# QiCape-v0_1.net
KiCad netlist of a schematic drawn in EAGLE
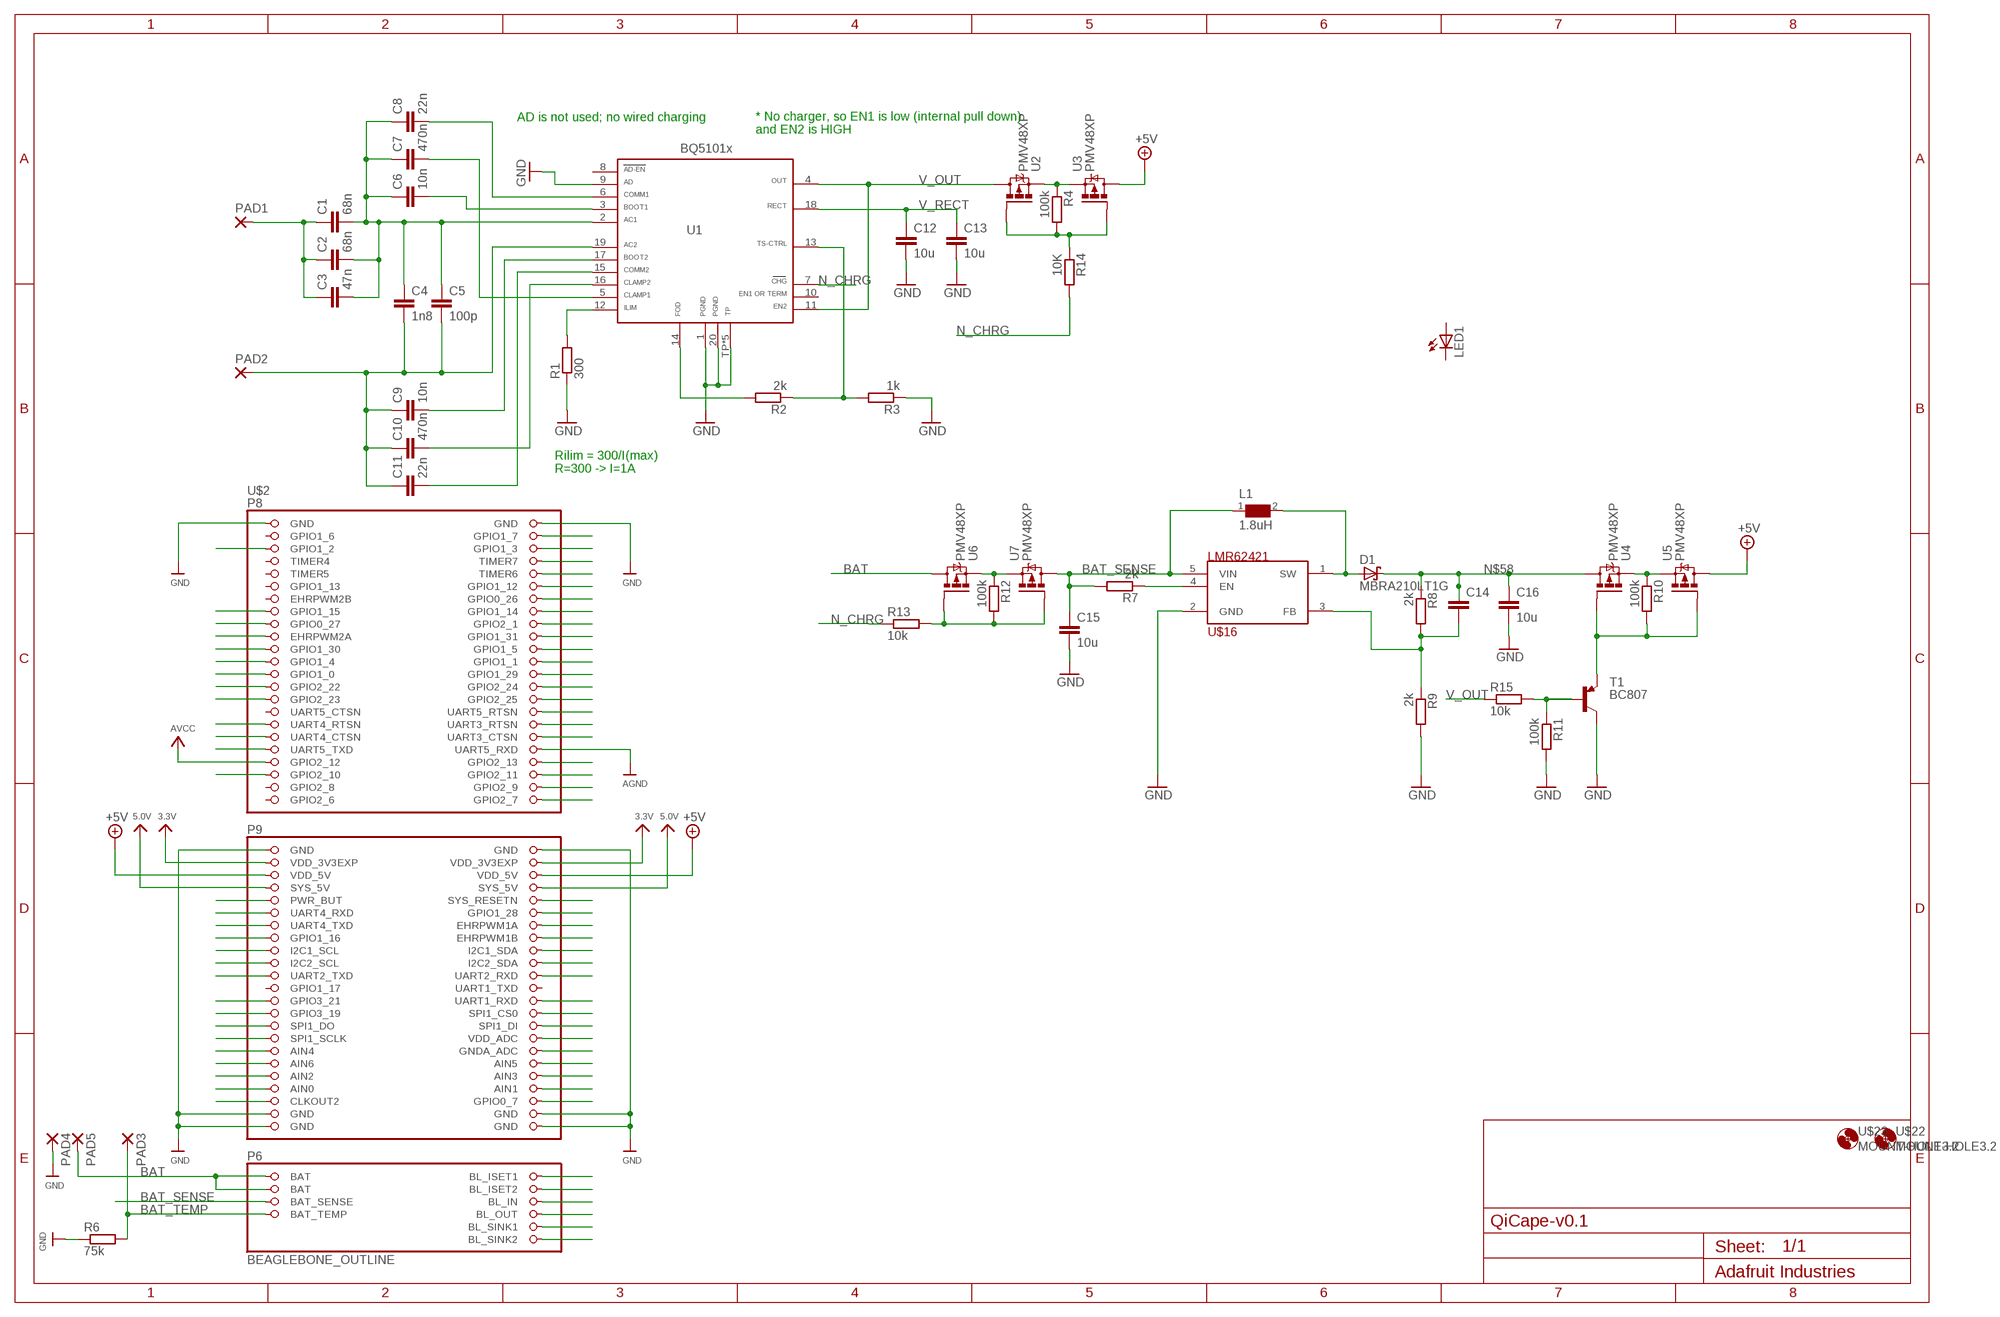
[diagram p0: schematic, sheet 1]

(export (version "E")
  (design (tool "Eeschema 10.0.6"))
  (components
    (comp (ref "C1")
      (value "68n")
      (footprint "eagle-import:C0603K")
      (fields (field (name "MF") "KEMET") (field (name "MPN") "C0603C682K5RACTU"))
      (libsource (lib "eagle-import") (part "C-EUC0603K"))
    )
    (comp (ref "C2")
      (value "68n")
      (footprint "eagle-import:C0603K")
      (fields (field (name "MF") "KEMET") (field (name "MPN") "C0603C682K5RACTU"))
      (libsource (lib "eagle-import") (part "C-EUC0603K"))
    )
    (comp (ref "C3")
      (value "47n")
      (footprint "eagle-import:C0603K")
      (fields (field (name "MPN") "C0603C473K5RACTU"))
      (libsource (lib "eagle-import") (part "C-EUC0603K"))
    )
    (comp (ref "C4")
      (value "1n8")
      (footprint "eagle-import:C0603K")
      (fields (field (name "MPN") "C0603C182K5RACTU"))
      (libsource (lib "eagle-import") (part "C-EUC0603K"))
    )
    (comp (ref "C5")
      (value "100p")
      (footprint "eagle-import:C0603K")
      (fields (field (name "MF") "KEMET") (field (name "MPN") "C0603C101K5RACTU"))
      (libsource (lib "eagle-import") (part "C-EUC0603K"))
    )
    (comp (ref "C6")
      (value "10n")
      (footprint "eagle-import:C0603K")
      (libsource (lib "eagle-import") (part "C-EUC0603K"))
    )
    (comp (ref "C7")
      (value "470n")
      (footprint "eagle-import:C0603K")
      (libsource (lib "eagle-import") (part "C-EUC0603K"))
    )
    (comp (ref "C8")
      (value "22n")
      (footprint "eagle-import:C0603K")
      (fields (field (name "MF") "KEMET") (field (name "MPN") "C0603C223K5RACTU"))
      (libsource (lib "eagle-import") (part "C-EUC0603K"))
    )
    (comp (ref "C9")
      (value "10n")
      (footprint "eagle-import:C0603K")
      (libsource (lib "eagle-import") (part "C-EUC0603K"))
    )
    (comp (ref "C10")
      (value "470n")
      (footprint "eagle-import:C0603K")
      (libsource (lib "eagle-import") (part "C-EUC0603K"))
    )
    (comp (ref "C11")
      (value "22n")
      (footprint "eagle-import:C0603K")
      (fields (field (name "MF") "KEMET") (field (name "MPN") "C0603C223K5RACTU"))
      (libsource (lib "eagle-import") (part "C-EUC0603K"))
    )
    (comp (ref "C12")
      (value "10u")
      (footprint "eagle-import:C0805")
      (fields (field (name "MPN") "GRM21BR61E106KA73L"))
      (libsource (lib "eagle-import") (part "C-EUC0805"))
    )
    (comp (ref "C13")
      (value "10u")
      (footprint "eagle-import:C0805")
      (fields (field (name "MPN") "GRM21BR61E106KA73L"))
      (libsource (lib "eagle-import") (part "C-EUC0805"))
    )
    (comp (ref "C14")
      (value "C-EUC0402")
      (footprint "eagle-import:C0402")
      (libsource (lib "eagle-import") (part "C-EUC0402"))
    )
    (comp (ref "C15")
      (value "10u")
      (footprint "eagle-import:C0805")
      (fields (field (name "MPN") "GRM21BR61E106KA73L"))
      (libsource (lib "eagle-import") (part "C-EUC0805"))
    )
    (comp (ref "C16")
      (value "10u")
      (footprint "eagle-import:C1206")
      (fields (field (name "MPN") "C3216X5R0J106K"))
      (libsource (lib "eagle-import") (part "C-EUC1206"))
    )
    (comp (ref "D1")
      (value "MBRA210LT1G")
      (footprint "eagle-import:SMA-DO214AC")
      (libsource (lib "eagle-import") (part "SCHOTTKY-DIODEMBRA210LT3G"))
    )
    (comp (ref "L1")
      (value "1.8uH")
      (footprint "eagle-import:WE-TPC_5818_5828")
      (fields (field (name "MPN") "7440520018"))
      (libsource (lib "eagle-import") (part "WE-TPC_5818/5828"))
    )
    (comp (ref "LED1")
      (value "LEDCHIP-LED0603")
      (footprint "eagle-import:CHIP-LED0603")
      (libsource (lib "eagle-import") (part "LEDCHIP-LED0603"))
    )
    (comp (ref "PAD1")
      (value "1,6/0,8")
      (footprint "eagle-import:1,6_0,8")
      (libsource (lib "eagle-import") (part "1,6/0,8"))
    )
    (comp (ref "PAD2")
      (value "1,6/0,8")
      (footprint "eagle-import:1,6_0,8")
      (libsource (lib "eagle-import") (part "1,6/0,8"))
    )
    (comp (ref "PAD3")
      (value "1,6/0,8")
      (footprint "eagle-import:1,6_0,8")
      (libsource (lib "eagle-import") (part "1,6/0,8"))
    )
    (comp (ref "PAD4")
      (value "1,6/0,8")
      (footprint "eagle-import:1,6_0,8")
      (libsource (lib "eagle-import") (part "1,6/0,8"))
    )
    (comp (ref "PAD5")
      (value "1,6/0,8")
      (footprint "eagle-import:1,6_0,8")
      (libsource (lib "eagle-import") (part "1,6/0,8"))
    )
    (comp (ref "R1")
      (value "300")
      (footprint "eagle-import:R0402")
      (fields (field (name "MPN") "ERJ3EKF3000V"))
      (libsource (lib "eagle-import") (part "R-EU_R0402"))
    )
    (comp (ref "R2")
      (value "2k")
      (footprint "eagle-import:R0402")
      (fields (field (name "MPN") "ERJ3EKF3000V"))
      (libsource (lib "eagle-import") (part "R-EU_R0402"))
    )
    (comp (ref "R3")
      (value "1k")
      (footprint "eagle-import:R0402")
      (fields (field (name "MPN") "ERJ3EKF3000V"))
      (libsource (lib "eagle-import") (part "R-EU_R0402"))
    )
    (comp (ref "R4")
      (value "100k")
      (footprint "eagle-import:R0402")
      (fields (field (name "MPN") "ERJ3EKF3000V"))
      (libsource (lib "eagle-import") (part "R-EU_R0402"))
    )
    (comp (ref "R6")
      (value "75k")
      (footprint "eagle-import:R0402")
      (fields (field (name "MPN") "ERJ3EKF3000V"))
      (libsource (lib "eagle-import") (part "R-EU_R0402"))
    )
    (comp (ref "R7")
      (value "2k")
      (footprint "eagle-import:R0402")
      (fields (field (name "MPN") "ERJ3EKF3000V"))
      (libsource (lib "eagle-import") (part "R-EU_R0402"))
    )
    (comp (ref "R8")
      (value "2k")
      (footprint "eagle-import:R0402")
      (fields (field (name "MPN") "ERJ3EKF3000V"))
      (libsource (lib "eagle-import") (part "R-EU_R0402"))
    )
    (comp (ref "R9")
      (value "2k")
      (footprint "eagle-import:R0402")
      (fields (field (name "MPN") "ERJ3EKF3000V"))
      (libsource (lib "eagle-import") (part "R-EU_R0402"))
    )
    (comp (ref "R10")
      (value "100k")
      (footprint "eagle-import:R0402")
      (fields (field (name "MPN") "ERJ3EKF3000V"))
      (libsource (lib "eagle-import") (part "R-EU_R0402"))
    )
    (comp (ref "R11")
      (value "100k")
      (footprint "eagle-import:R0402")
      (fields (field (name "MPN") "ERJ3EKF3000V"))
      (libsource (lib "eagle-import") (part "R-EU_R0402"))
    )
    (comp (ref "R12")
      (value "100k")
      (footprint "eagle-import:R0402")
      (fields (field (name "MPN") "ERJ3EKF3000V"))
      (libsource (lib "eagle-import") (part "R-EU_R0402"))
    )
    (comp (ref "R13")
      (value "10k")
      (footprint "eagle-import:R0402")
      (fields (field (name "MPN") "ERJ3EKF3000V"))
      (libsource (lib "eagle-import") (part "R-EU_R0402"))
    )
    (comp (ref "R14")
      (value "10K")
      (footprint "eagle-import:R0402")
      (fields (field (name "MPN") "ERJ3EKF3000V"))
      (libsource (lib "eagle-import") (part "R-EU_R0402"))
    )
    (comp (ref "R15")
      (value "10k")
      (footprint "eagle-import:R0402")
      (fields (field (name "MPN") "ERJ3EKF3000V"))
      (libsource (lib "eagle-import") (part "R-EU_R0402"))
    )
    (comp (ref "T1")
      (value "BC807")
      (footprint "eagle-import:SOT23-BEC")
      (libsource (lib "eagle-import") (part "-PNP-SOT23-BECBC807-16"))
    )
    (comp (ref "U$2")
      (value "BEAGLEBONE_OUTLINE")
      (footprint "eagle-import:BEAGLEBONE_SHIELD_VS")
      (libsource (lib "eagle-import") (part "BEAGLEBONE_OUTLINE"))
    )
    (comp (ref "U$16")
      (value "LMR62421")
      (footprint "eagle-import:SOT23-5")
      (libsource (lib "eagle-import") (part "LMR62421"))
    )
    (comp (ref "U$22")
      (value "MOUNT-HOLE3.2")
      (footprint "eagle-import:3,2")
      (libsource (lib "eagle-import") (part "MOUNT-HOLE3.2"))
    )
    (comp (ref "U$23")
      (value "MOUNT-HOLE3.2")
      (footprint "eagle-import:3,2")
      (libsource (lib "eagle-import") (part "MOUNT-HOLE3.2"))
    )
    (comp (ref "U1")
      (value "BQ51013ARHL20")
      (footprint "eagle-import:RHL")
      (fields (field (name "MPN") "BQ51013ARHLT"))
      (libsource (lib "eagle-import") (part "BQ51013ARHL20"))
    )
    (comp (ref "U2")
      (value "PMV48XP")
      (footprint "eagle-import:SOT95P230X110-3N")
      (libsource (lib "eagle-import") (part "PMV48XP"))
    )
    (comp (ref "U3")
      (value "PMV48XP")
      (footprint "eagle-import:SOT95P230X110-3N")
      (libsource (lib "eagle-import") (part "PMV48XP"))
    )
    (comp (ref "U4")
      (value "PMV48XP")
      (footprint "eagle-import:SOT95P230X110-3N")
      (libsource (lib "eagle-import") (part "PMV48XP"))
    )
    (comp (ref "U5")
      (value "PMV48XP")
      (footprint "eagle-import:SOT95P230X110-3N")
      (libsource (lib "eagle-import") (part "PMV48XP"))
    )
    (comp (ref "U6")
      (value "PMV48XP")
      (footprint "eagle-import:SOT95P230X110-3N")
      (libsource (lib "eagle-import") (part "PMV48XP"))
    )
    (comp (ref "U7")
      (value "PMV48XP")
      (footprint "eagle-import:SOT95P230X110-3N")
      (libsource (lib "eagle-import") (part "PMV48XP"))
    )
  )
  (nets
    (net (code "1") (name "+5V") (class "Default")
      (node (ref "U$2") (pin "51") (pinfunction "VDD_5V_51") (pintype "power_in"))
      (node (ref "U$2") (pin "52") (pinfunction "VDD_5V_52") (pintype "power_in"))
      (node (ref "U3") (pin "3") (pinfunction "D_3") (pintype "passive"))
      (node (ref "U5") (pin "3") (pinfunction "D_3") (pintype "passive"))
    )
    (net (code "2") (name "/BAT") (class "Default")
      (node (ref "PAD5") (pin "1") (pinfunction "P_1") (pintype "passive"))
      (node (ref "U$2") (pin "1_BAT") (pinfunction "BAT_1_BAT") (pintype "power_in"))
      (node (ref "U$2") (pin "2_BAT") (pinfunction "BAT_2_BAT") (pintype "power_in"))
      (node (ref "U6") (pin "3") (pinfunction "D_3") (pintype "passive"))
    )
    (net (code "3") (name "/BAT_SENSE") (class "Default")
      (node (ref "C15") (pin "1") (pinfunction "1_1") (pintype "passive"))
      (node (ref "L1") (pin "1") (pinfunction "1_1") (pintype "passive"))
      (node (ref "R7") (pin "2") (pinfunction "2_2") (pintype "passive"))
      (node (ref "U$16") (pin "5") (pinfunction "VIN_5") (pintype "power_in"))
      (node (ref "U$2") (pin "3_BAT_SENSE") (pinfunction "BAT_SENSE_3_BAT_SENSE") (pintype "passive"))
      (node (ref "U7") (pin "3") (pinfunction "D_3") (pintype "passive"))
    )
    (net (code "4") (name "/BAT_TEMP") (class "Default")
      (node (ref "PAD3") (pin "1") (pinfunction "P_1") (pintype "passive"))
      (node (ref "R6") (pin "2") (pinfunction "2_2") (pintype "passive"))
      (node (ref "U$2") (pin "4_BAT_TEMP") (pinfunction "BAT_TEMP_4_BAT_TEMP") (pintype "passive"))
    )
    (net (code "5") (name "/GPIO1_6") (class "Default")
      (node (ref "U$2") (pin "3") (pinfunction "GPIO1_6_3") (pintype "power_in"))
    )
    (net (code "6") (name "/GPIO2_6") (class "Default")
      (node (ref "U$2") (pin "45") (pinfunction "GPIO2_6_45") (pintype "power_in"))
    )
    (net (code "7") (name "/GPIO2_8") (class "Default")
      (node (ref "U$2") (pin "43") (pinfunction "GPIO2_8_43") (pintype "power_in"))
    )
    (net (code "8") (name "/N$58") (class "Default")
      (node (ref "C14") (pin "1") (pinfunction "1_1") (pintype "passive"))
      (node (ref "C16") (pin "1") (pinfunction "1_1") (pintype "passive"))
      (node (ref "D1") (pin "K") (pinfunction "C_K") (pintype "passive"))
      (node (ref "R8") (pin "1") (pinfunction "1_1") (pintype "passive"))
      (node (ref "U4") (pin "3") (pinfunction "D_3") (pintype "passive"))
    )
    (net (code "9") (name "/N_CHRG") (class "Default")
      (node (ref "R13") (pin "1") (pinfunction "1_1") (pintype "passive"))
      (node (ref "R14") (pin "2") (pinfunction "2_2") (pintype "passive"))
      (node (ref "U1") (pin "7") (pinfunction "7_7") (pintype "bidirectional"))
    )
    (net (code "10") (name "/V_OUT") (class "Default")
      (node (ref "R15") (pin "1") (pinfunction "1_1") (pintype "passive"))
      (node (ref "U1") (pin "11") (pinfunction "11_11") (pintype "bidirectional"))
      (node (ref "U1") (pin "4") (pinfunction "4_4") (pintype "bidirectional"))
      (node (ref "U2") (pin "3") (pinfunction "D_3") (pintype "passive"))
    )
    (net (code "11") (name "/V_RECT") (class "Default")
      (node (ref "C12") (pin "1") (pinfunction "1_1") (pintype "passive"))
      (node (ref "C13") (pin "1") (pinfunction "1_1") (pintype "passive"))
      (node (ref "U1") (pin "18") (pinfunction "18_18") (pintype "bidirectional"))
    )
    (net (code "12") (name "3.3V") (class "Default")
      (node (ref "U$2") (pin "49") (pinfunction "VDD_3V3EXP_49") (pintype "power_in"))
      (node (ref "U$2") (pin "50") (pinfunction "VDD_3V3EXP_50") (pintype "power_in"))
    )
    (net (code "13") (name "5.0V") (class "Default")
      (node (ref "U$2") (pin "53") (pinfunction "SYS_5V_53") (pintype "passive"))
      (node (ref "U$2") (pin "54") (pinfunction "SYS_5V_54") (pintype "passive"))
    )
    (net (code "14") (name "AGND") (class "Default")
      (node (ref "U$2") (pin "38") (pinfunction "UART5_RXD_38") (pintype "passive"))
    )
    (net (code "15") (name "AVCC") (class "Default")
      (node (ref "U$2") (pin "39") (pinfunction "GPIO2_12_39") (pintype "passive"))
    )
    (net (code "16") (name "GND") (class "Default")
      (node (ref "C12") (pin "2") (pinfunction "2_2") (pintype "passive"))
      (node (ref "C13") (pin "2") (pinfunction "2_2") (pintype "passive"))
      (node (ref "C15") (pin "2") (pinfunction "2_2") (pintype "passive"))
      (node (ref "C16") (pin "2") (pinfunction "2_2") (pintype "passive"))
      (node (ref "PAD4") (pin "1") (pinfunction "P_1") (pintype "passive"))
      (node (ref "R1") (pin "1") (pinfunction "1_1") (pintype "passive"))
      (node (ref "R11") (pin "2") (pinfunction "2_2") (pintype "passive"))
      (node (ref "R3") (pin "1") (pinfunction "1_1") (pintype "passive"))
      (node (ref "R6") (pin "1") (pinfunction "1_1") (pintype "passive"))
      (node (ref "R9") (pin "2") (pinfunction "2_2") (pintype "passive"))
      (node (ref "T1") (pin "C") (pinfunction "C_C") (pintype "passive"))
      (node (ref "U$16") (pin "2") (pinfunction "GND_2") (pintype "power_in"))
      (node (ref "U$2") (pin "1") (pinfunction "GND_1") (pintype "power_in"))
      (node (ref "U$2") (pin "2") (pinfunction "GND_2") (pintype "power_in"))
      (node (ref "U$2") (pin "47") (pinfunction "GND_47") (pintype "power_in"))
      (node (ref "U$2") (pin "48") (pinfunction "GND_48") (pintype "power_in"))
      (node (ref "U$2") (pin "89") (pinfunction "GND_89") (pintype "input"))
      (node (ref "U$2") (pin "90") (pinfunction "GND_90") (pintype "input"))
      (node (ref "U$2") (pin "91") (pinfunction "GND_91") (pintype "input"))
      (node (ref "U$2") (pin "92") (pinfunction "GND_92") (pintype "input"))
      (node (ref "U1") (pin "1") (pinfunction "1_1") (pintype "bidirectional"))
      (node (ref "U1") (pin "20") (pinfunction "20_20") (pintype "bidirectional"))
      (node (ref "U1") (pin "9") (pinfunction "9_9") (pintype "bidirectional"))
      (node (ref "U1") (pin "TP") (pinfunction "TP_TP") (pintype "bidirectional"))
      (node (ref "U1") (pin "TP1") (pinfunction "TP_TP1") (pintype "bidirectional"))
      (node (ref "U1") (pin "TP2") (pinfunction "TP_TP2") (pintype "bidirectional"))
      (node (ref "U1") (pin "TP3") (pinfunction "TP_TP3") (pintype "bidirectional"))
      (node (ref "U1") (pin "TP4") (pinfunction "TP_TP4") (pintype "bidirectional"))
    )
    (net (code "17") (name "Net-(C1-Pad2)") (class "Default")
      (node (ref "C1") (pin "2") (pinfunction "2_2") (pintype "passive"))
      (node (ref "C2") (pin "2") (pinfunction "2_2") (pintype "passive"))
      (node (ref "C3") (pin "2") (pinfunction "2_2") (pintype "passive"))
      (node (ref "C4") (pin "1") (pinfunction "1_1") (pintype "passive"))
      (node (ref "C5") (pin "1") (pinfunction "1_1") (pintype "passive"))
      (node (ref "C6") (pin "1") (pinfunction "1_1") (pintype "passive"))
      (node (ref "C7") (pin "1") (pinfunction "1_1") (pintype "passive"))
      (node (ref "C8") (pin "1") (pinfunction "1_1") (pintype "passive"))
      (node (ref "U1") (pin "2") (pinfunction "2_2") (pintype "bidirectional"))
    )
    (net (code "18") (name "Net-(C6-Pad2)") (class "Default")
      (node (ref "C6") (pin "2") (pinfunction "2_2") (pintype "passive"))
      (node (ref "U1") (pin "3") (pinfunction "3_3") (pintype "bidirectional"))
    )
    (net (code "19") (name "Net-(C7-Pad2)") (class "Default")
      (node (ref "C7") (pin "2") (pinfunction "2_2") (pintype "passive"))
      (node (ref "U1") (pin "5") (pinfunction "5_5") (pintype "bidirectional"))
    )
    (net (code "20") (name "Net-(C8-Pad2)") (class "Default")
      (node (ref "C8") (pin "2") (pinfunction "2_2") (pintype "passive"))
      (node (ref "U1") (pin "6") (pinfunction "6_6") (pintype "bidirectional"))
    )
    (net (code "21") (name "Net-(C9-Pad2)") (class "Default")
      (node (ref "C9") (pin "2") (pinfunction "2_2") (pintype "passive"))
      (node (ref "U1") (pin "17") (pinfunction "17_17") (pintype "bidirectional"))
    )
    (net (code "22") (name "Net-(C10-Pad2)") (class "Default")
      (node (ref "C10") (pin "2") (pinfunction "2_2") (pintype "passive"))
      (node (ref "U1") (pin "16") (pinfunction "16_16") (pintype "bidirectional"))
    )
    (net (code "23") (name "Net-(C11-Pad2)") (class "Default")
      (node (ref "C11") (pin "2") (pinfunction "2_2") (pintype "passive"))
      (node (ref "U1") (pin "15") (pinfunction "15_15") (pintype "bidirectional"))
    )
    (net (code "24") (name "Net-(PAD1-P)") (class "Default")
      (node (ref "C1") (pin "1") (pinfunction "1_1") (pintype "passive"))
      (node (ref "C2") (pin "1") (pinfunction "1_1") (pintype "passive"))
      (node (ref "C3") (pin "1") (pinfunction "1_1") (pintype "passive"))
      (node (ref "PAD1") (pin "1") (pinfunction "P_1") (pintype "passive"))
    )
    (net (code "25") (name "Net-(PAD2-P)") (class "Default")
      (node (ref "C10") (pin "1") (pinfunction "1_1") (pintype "passive"))
      (node (ref "C11") (pin "1") (pinfunction "1_1") (pintype "passive"))
      (node (ref "C4") (pin "2") (pinfunction "2_2") (pintype "passive"))
      (node (ref "C5") (pin "2") (pinfunction "2_2") (pintype "passive"))
      (node (ref "C9") (pin "1") (pinfunction "1_1") (pintype "passive"))
      (node (ref "PAD2") (pin "1") (pinfunction "P_1") (pintype "passive"))
      (node (ref "U1") (pin "19") (pinfunction "19_19") (pintype "bidirectional"))
    )
    (net (code "26") (name "Net-(R1-Pad2)") (class "Default")
      (node (ref "R1") (pin "2") (pinfunction "2_2") (pintype "passive"))
      (node (ref "U1") (pin "12") (pinfunction "12_12") (pintype "bidirectional"))
    )
    (net (code "27") (name "Net-(R2-Pad1)") (class "Default")
      (node (ref "R2") (pin "1") (pinfunction "1_1") (pintype "passive"))
      (node (ref "R3") (pin "2") (pinfunction "2_2") (pintype "passive"))
      (node (ref "U1") (pin "13") (pinfunction "13_13") (pintype "bidirectional"))
    )
    (net (code "28") (name "Net-(R2-Pad2)") (class "Default")
      (node (ref "R2") (pin "2") (pinfunction "2_2") (pintype "passive"))
      (node (ref "U1") (pin "14") (pinfunction "14_14") (pintype "bidirectional"))
    )
    (net (code "29") (name "Net-(R11-Pad1)") (class "Default")
      (node (ref "R11") (pin "1") (pinfunction "1_1") (pintype "passive"))
      (node (ref "R15") (pin "2") (pinfunction "2_2") (pintype "passive"))
      (node (ref "T1") (pin "B") (pinfunction "B_B") (pintype "passive"))
    )
    (net (code "30") (name "Net-(U$16-EN)") (class "Default")
      (node (ref "R7") (pin "1") (pinfunction "1_1") (pintype "passive"))
      (node (ref "U$16") (pin "4") (pinfunction "EN_4") (pintype "input"))
    )
    (net (code "31") (name "Net-(U$16-FB)") (class "Default")
      (node (ref "C14") (pin "2") (pinfunction "2_2") (pintype "passive"))
      (node (ref "R8") (pin "2") (pinfunction "2_2") (pintype "passive"))
      (node (ref "R9") (pin "1") (pinfunction "1_1") (pintype "passive"))
      (node (ref "U$16") (pin "3") (pinfunction "FB_3") (pintype "passive"))
    )
    (net (code "32") (name "Net-(U$16-SW)") (class "Default")
      (node (ref "D1") (pin "A") (pinfunction "A_A") (pintype "passive"))
      (node (ref "L1") (pin "2") (pinfunction "2_2") (pintype "passive"))
      (node (ref "U$16") (pin "1") (pinfunction "SW_1") (pintype "output"))
    )
    (net (code "33") (name "Net-(U2-G)") (class "Default")
      (node (ref "R14") (pin "1") (pinfunction "1_1") (pintype "passive"))
      (node (ref "R4") (pin "2") (pinfunction "2_2") (pintype "passive"))
      (node (ref "U2") (pin "1") (pinfunction "G_1") (pintype "passive"))
      (node (ref "U3") (pin "1") (pinfunction "G_1") (pintype "passive"))
    )
    (net (code "34") (name "Net-(U2-S)") (class "Default")
      (node (ref "R4") (pin "1") (pinfunction "1_1") (pintype "passive"))
      (node (ref "U2") (pin "2") (pinfunction "S_2") (pintype "passive"))
      (node (ref "U3") (pin "2") (pinfunction "S_2") (pintype "passive"))
    )
    (net (code "35") (name "Net-(U4-G)") (class "Default")
      (node (ref "R10") (pin "2") (pinfunction "2_2") (pintype "passive"))
      (node (ref "T1") (pin "E") (pinfunction "E_E") (pintype "passive"))
      (node (ref "U4") (pin "1") (pinfunction "G_1") (pintype "passive"))
      (node (ref "U5") (pin "1") (pinfunction "G_1") (pintype "passive"))
    )
    (net (code "36") (name "Net-(U4-S)") (class "Default")
      (node (ref "R10") (pin "1") (pinfunction "1_1") (pintype "passive"))
      (node (ref "U4") (pin "2") (pinfunction "S_2") (pintype "passive"))
      (node (ref "U5") (pin "2") (pinfunction "S_2") (pintype "passive"))
    )
    (net (code "37") (name "Net-(U6-G)") (class "Default")
      (node (ref "R12") (pin "2") (pinfunction "2_2") (pintype "passive"))
      (node (ref "R13") (pin "2") (pinfunction "2_2") (pintype "passive"))
      (node (ref "U6") (pin "1") (pinfunction "G_1") (pintype "passive"))
      (node (ref "U7") (pin "1") (pinfunction "G_1") (pintype "passive"))
    )
    (net (code "38") (name "Net-(U6-S)") (class "Default")
      (node (ref "R12") (pin "1") (pinfunction "1_1") (pintype "passive"))
      (node (ref "U6") (pin "2") (pinfunction "S_2") (pintype "passive"))
      (node (ref "U7") (pin "2") (pinfunction "S_2") (pintype "passive"))
    )
    (net (code "39") (name "unconnected-(LED1-PadA)") (class "Default")
      (node (ref "LED1") (pin "A") (pinfunction "A_A") (pintype "passive"))
    )
    (net (code "40") (name "unconnected-(LED1-PadC)") (class "Default")
      (node (ref "LED1") (pin "C") (pinfunction "C_C") (pintype "passive"))
    )
    (net (code "41") (name "unconnected-(U$2-AIN0-Pad85)") (class "Default")
      (node (ref "U$2") (pin "85") (pinfunction "AIN0_85") (pintype "power_in"))
    )
    (net (code "42") (name "unconnected-(U$2-AIN1-Pad86)") (class "Default")
      (node (ref "U$2") (pin "86") (pinfunction "AIN1_86") (pintype "input"))
    )
    (net (code "43") (name "unconnected-(U$2-AIN2-Pad83)") (class "Default")
      (node (ref "U$2") (pin "83") (pinfunction "AIN2_83") (pintype "passive"))
    )
    (net (code "44") (name "unconnected-(U$2-AIN3-Pad84)") (class "Default")
      (node (ref "U$2") (pin "84") (pinfunction "AIN3_84") (pintype "power_in"))
    )
    (net (code "45") (name "unconnected-(U$2-AIN4-Pad79)") (class "Default")
      (node (ref "U$2") (pin "79") (pinfunction "AIN4_79") (pintype "passive"))
    )
    (net (code "46") (name "unconnected-(U$2-AIN5-Pad82)") (class "Default")
      (node (ref "U$2") (pin "82") (pinfunction "AIN5_82") (pintype "passive"))
    )
    (net (code "47") (name "unconnected-(U$2-AIN6-Pad81)") (class "Default")
      (node (ref "U$2") (pin "81") (pinfunction "AIN6_81") (pintype "passive"))
    )
    (net (code "48") (name "unconnected-(U$2-BL_IN-Pad8_BL_IN)") (class "Default")
      (node (ref "U$2") (pin "8_BL_IN") (pinfunction "BL_IN_8_BL_IN") (pintype "power_in"))
    )
    (net (code "49") (name "unconnected-(U$2-BL_ISET1-Pad6_BL_ISET1)") (class "Default")
      (node (ref "U$2") (pin "6_BL_ISET1") (pinfunction "BL_ISET1_6_BL_ISET1") (pintype "input"))
    )
    (net (code "50") (name "unconnected-(U$2-BL_ISET2-Pad5_BL_ISET2)") (class "Default")
      (node (ref "U$2") (pin "5_BL_ISET2") (pinfunction "BL_ISET2_5_BL_ISET2") (pintype "input"))
    )
    (net (code "51") (name "unconnected-(U$2-BL_OUT-Pad7_BL_OUT)") (class "Default")
      (node (ref "U$2") (pin "7_BL_OUT") (pinfunction "BL_OUT_7_BL_OUT") (pintype "power_in"))
    )
    (net (code "52") (name "unconnected-(U$2-BL_SINK1-Pad9_BL_SINK1)") (class "Default")
      (node (ref "U$2") (pin "9_BL_SINK1") (pinfunction "BL_SINK1_9_BL_SINK1") (pintype "passive"))
    )
    (net (code "53") (name "unconnected-(U$2-BL_SINK2-Pad10_BL_SINK2)") (class "Default")
      (node (ref "U$2") (pin "10_BL_SINK2") (pinfunction "BL_SINK2_10_BL_SINK2") (pintype "passive"))
    )
    (net (code "54") (name "unconnected-(U$2-CLKOUT2-Pad87)") (class "Default")
      (node (ref "U$2") (pin "87") (pinfunction "CLKOUT2_87") (pintype "input"))
    )
    (net (code "55") (name "unconnected-(U$2-EHRPWM1A-Pad60)") (class "Default")
      (node (ref "U$2") (pin "60") (pinfunction "EHRPWM1A_60") (pintype "passive"))
    )
    (net (code "56") (name "unconnected-(U$2-EHRPWM1B-Pad62)") (class "Default")
      (node (ref "U$2") (pin "62") (pinfunction "EHRPWM1B_62") (pintype "passive"))
    )
    (net (code "57") (name "unconnected-(U$2-EHRPWM2A-Pad19)") (class "Default")
      (node (ref "U$2") (pin "19") (pinfunction "EHRPWM2A_19") (pintype "passive"))
    )
    (net (code "58") (name "unconnected-(U$2-EHRPWM2B-Pad13)") (class "Default")
      (node (ref "U$2") (pin "13") (pinfunction "EHRPWM2B_13") (pintype "passive"))
    )
    (net (code "59") (name "unconnected-(U$2-GNDA_ADC-Pad80)") (class "Default")
      (node (ref "U$2") (pin "80") (pinfunction "GNDA_ADC_80") (pintype "passive"))
    )
    (net (code "60") (name "unconnected-(U$2-GPIO0_7-Pad88)") (class "Default")
      (node (ref "U$2") (pin "88") (pinfunction "GPIO0_7_88") (pintype "input"))
    )
    (net (code "61") (name "unconnected-(U$2-GPIO0_26-Pad14)") (class "Default")
      (node (ref "U$2") (pin "14") (pinfunction "GPIO0_26_14") (pintype "passive"))
    )
    (net (code "62") (name "unconnected-(U$2-GPIO0_27-Pad17)") (class "Default")
      (node (ref "U$2") (pin "17") (pinfunction "GPIO0_27_17") (pintype "passive"))
    )
    (net (code "63") (name "unconnected-(U$2-GPIO1_0-Pad25)") (class "Default")
      (node (ref "U$2") (pin "25") (pinfunction "GPIO1_0_25") (pintype "passive"))
    )
    (net (code "64") (name "unconnected-(U$2-GPIO1_1-Pad24)") (class "Default")
      (node (ref "U$2") (pin "24") (pinfunction "GPIO1_1_24") (pintype "passive"))
    )
    (net (code "65") (name "unconnected-(U$2-GPIO1_2-Pad5)") (class "Default")
      (node (ref "U$2") (pin "5") (pinfunction "GPIO1_2_5") (pintype "passive"))
    )
    (net (code "66") (name "unconnected-(U$2-GPIO1_3-Pad6)") (class "Default")
      (node (ref "U$2") (pin "6") (pinfunction "GPIO1_3_6") (pintype "passive"))
    )
    (net (code "67") (name "unconnected-(U$2-GPIO1_4-Pad23)") (class "Default")
      (node (ref "U$2") (pin "23") (pinfunction "GPIO1_4_23") (pintype "passive"))
    )
    (net (code "68") (name "unconnected-(U$2-GPIO1_5-Pad22)") (class "Default")
      (node (ref "U$2") (pin "22") (pinfunction "GPIO1_5_22") (pintype "passive"))
    )
    (net (code "69") (name "unconnected-(U$2-GPIO1_7-Pad4)") (class "Default")
      (node (ref "U$2") (pin "4") (pinfunction "GPIO1_7_4") (pintype "power_in"))
    )
    (net (code "70") (name "unconnected-(U$2-GPIO1_12-Pad12)") (class "Default")
      (node (ref "U$2") (pin "12") (pinfunction "GPIO1_12_12") (pintype "passive"))
    )
    (net (code "71") (name "unconnected-(U$2-GPIO1_13-Pad11)") (class "Default")
      (node (ref "U$2") (pin "11") (pinfunction "GPIO1_13_11") (pintype "passive"))
    )
    (net (code "72") (name "unconnected-(U$2-GPIO1_14-Pad16)") (class "Default")
      (node (ref "U$2") (pin "16") (pinfunction "GPIO1_14_16") (pintype "passive"))
    )
    (net (code "73") (name "unconnected-(U$2-GPIO1_15-Pad15)") (class "Default")
      (node (ref "U$2") (pin "15") (pinfunction "GPIO1_15_15") (pintype "passive"))
    )
    (net (code "74") (name "unconnected-(U$2-GPIO1_16-Pad61)") (class "Default")
      (node (ref "U$2") (pin "61") (pinfunction "GPIO1_16_61") (pintype "passive"))
    )
    (net (code "75") (name "unconnected-(U$2-GPIO1_17-Pad69)") (class "Default")
      (node (ref "U$2") (pin "69") (pinfunction "GPIO1_17_69") (pintype "passive"))
    )
    (net (code "76") (name "unconnected-(U$2-GPIO1_28-Pad58)") (class "Default")
      (node (ref "U$2") (pin "58") (pinfunction "GPIO1_28_58") (pintype "passive"))
    )
    (net (code "77") (name "unconnected-(U$2-GPIO1_29-Pad26)") (class "Default")
      (node (ref "U$2") (pin "26") (pinfunction "GPIO1_29_26") (pintype "passive"))
    )
    (net (code "78") (name "unconnected-(U$2-GPIO1_30-Pad21)") (class "Default")
      (node (ref "U$2") (pin "21") (pinfunction "GPIO1_30_21") (pintype "passive"))
    )
    (net (code "79") (name "unconnected-(U$2-GPIO1_31-Pad20)") (class "Default")
      (node (ref "U$2") (pin "20") (pinfunction "GPIO1_31_20") (pintype "passive"))
    )
    (net (code "80") (name "unconnected-(U$2-GPIO2_1-Pad18)") (class "Default")
      (node (ref "U$2") (pin "18") (pinfunction "GPIO2_1_18") (pintype "passive"))
    )
    (net (code "81") (name "unconnected-(U$2-GPIO2_7-Pad46)") (class "Default")
      (node (ref "U$2") (pin "46") (pinfunction "GPIO2_7_46") (pintype "power_in"))
    )
    (net (code "82") (name "unconnected-(U$2-GPIO2_9-Pad44)") (class "Default")
      (node (ref "U$2") (pin "44") (pinfunction "GPIO2_9_44") (pintype "power_in"))
    )
    (net (code "83") (name "unconnected-(U$2-GPIO2_10-Pad41)") (class "Default")
      (node (ref "U$2") (pin "41") (pinfunction "GPIO2_10_41") (pintype "passive"))
    )
    (net (code "84") (name "unconnected-(U$2-GPIO2_11-Pad42)") (class "Default")
      (node (ref "U$2") (pin "42") (pinfunction "GPIO2_11_42") (pintype "power_in"))
    )
    (net (code "85") (name "unconnected-(U$2-GPIO2_13-Pad40)") (class "Default")
      (node (ref "U$2") (pin "40") (pinfunction "GPIO2_13_40") (pintype "passive"))
    )
    (net (code "86") (name "unconnected-(U$2-GPIO2_22-Pad27)") (class "Default")
      (node (ref "U$2") (pin "27") (pinfunction "GPIO2_22_27") (pintype "passive"))
    )
    (net (code "87") (name "unconnected-(U$2-GPIO2_23-Pad29)") (class "Default")
      (node (ref "U$2") (pin "29") (pinfunction "GPIO2_23_29") (pintype "passive"))
    )
    (net (code "88") (name "unconnected-(U$2-GPIO2_24-Pad28)") (class "Default")
      (node (ref "U$2") (pin "28") (pinfunction "GPIO2_24_28") (pintype "passive"))
    )
    (net (code "89") (name "unconnected-(U$2-GPIO2_25-Pad30)") (class "Default")
      (node (ref "U$2") (pin "30") (pinfunction "GPIO2_25_30") (pintype "passive"))
    )
    (net (code "90") (name "unconnected-(U$2-GPIO3_19-Pad73)") (class "Default")
      (node (ref "U$2") (pin "73") (pinfunction "GPIO3_19_73") (pintype "passive"))
    )
    (net (code "91") (name "unconnected-(U$2-GPIO3_21-Pad71)") (class "Default")
      (node (ref "U$2") (pin "71") (pinfunction "GPIO3_21_71") (pintype "passive"))
    )
    (net (code "92") (name "unconnected-(U$2-I2C1_SCL-Pad63)") (class "Default")
      (node (ref "U$2") (pin "63") (pinfunction "I2C1_SCL_63") (pintype "passive"))
    )
    (net (code "93") (name "unconnected-(U$2-I2C1_SDA-Pad64)") (class "Default")
      (node (ref "U$2") (pin "64") (pinfunction "I2C1_SDA_64") (pintype "passive"))
    )
    (net (code "94") (name "unconnected-(U$2-I2C2_SCL-Pad65)") (class "Default")
      (node (ref "U$2") (pin "65") (pinfunction "I2C2_SCL_65") (pintype "passive"))
    )
    (net (code "95") (name "unconnected-(U$2-I2C2_SDA-Pad66)") (class "Default")
      (node (ref "U$2") (pin "66") (pinfunction "I2C2_SDA_66") (pintype "passive"))
    )
    (net (code "96") (name "unconnected-(U$2-PWR_BUT-Pad55)") (class "Default")
      (node (ref "U$2") (pin "55") (pinfunction "PWR_BUT_55") (pintype "passive"))
    )
    (net (code "97") (name "unconnected-(U$2-SPI1_CS0-Pad74)") (class "Default")
      (node (ref "U$2") (pin "74") (pinfunction "SPI1_CS0_74") (pintype "passive"))
    )
    (net (code "98") (name "unconnected-(U$2-SPI1_DI-Pad76)") (class "Default")
      (node (ref "U$2") (pin "76") (pinfunction "SPI1_DI_76") (pintype "passive"))
    )
    (net (code "99") (name "unconnected-(U$2-SPI1_DO-Pad75)") (class "Default")
      (node (ref "U$2") (pin "75") (pinfunction "SPI1_DO_75") (pintype "passive"))
    )
    (net (code "100") (name "unconnected-(U$2-SPI1_SCLK-Pad77)") (class "Default")
      (node (ref "U$2") (pin "77") (pinfunction "SPI1_SCLK_77") (pintype "passive"))
    )
    (net (code "101") (name "unconnected-(U$2-SYS_RESETN-Pad56)") (class "Default")
      (node (ref "U$2") (pin "56") (pinfunction "SYS_RESETN_56") (pintype "passive"))
    )
    (net (code "102") (name "unconnected-(U$2-TIMER4-Pad7)") (class "Default")
      (node (ref "U$2") (pin "7") (pinfunction "TIMER4_7") (pintype "passive"))
    )
    (net (code "103") (name "unconnected-(U$2-TIMER5-Pad9)") (class "Default")
      (node (ref "U$2") (pin "9") (pinfunction "TIMER5_9") (pintype "passive"))
    )
    (net (code "104") (name "unconnected-(U$2-TIMER6-Pad10)") (class "Default")
      (node (ref "U$2") (pin "10") (pinfunction "TIMER6_10") (pintype "passive"))
    )
    (net (code "105") (name "unconnected-(U$2-TIMER7-Pad8)") (class "Default")
      (node (ref "U$2") (pin "8") (pinfunction "TIMER7_8") (pintype "passive"))
    )
    (net (code "106") (name "unconnected-(U$2-UART1_RXD-Pad72)") (class "Default")
      (node (ref "U$2") (pin "72") (pinfunction "UART1_RXD_72") (pintype "passive"))
    )
    (net (code "107") (name "unconnected-(U$2-UART1_TXD-Pad70)") (class "Default")
      (node (ref "U$2") (pin "70") (pinfunction "UART1_TXD_70") (pintype "passive"))
    )
    (net (code "108") (name "unconnected-(U$2-UART2_RXD-Pad68)") (class "Default")
      (node (ref "U$2") (pin "68") (pinfunction "UART2_RXD_68") (pintype "passive"))
    )
    (net (code "109") (name "unconnected-(U$2-UART2_TXD-Pad67)") (class "Default")
      (node (ref "U$2") (pin "67") (pinfunction "UART2_TXD_67") (pintype "passive"))
    )
    (net (code "110") (name "unconnected-(U$2-UART3_CTSN-Pad36)") (class "Default")
      (node (ref "U$2") (pin "36") (pinfunction "UART3_CTSN_36") (pintype "passive"))
    )
    (net (code "111") (name "unconnected-(U$2-UART3_RTSN-Pad34)") (class "Default")
      (node (ref "U$2") (pin "34") (pinfunction "UART3_RTSN_34") (pintype "passive"))
    )
    (net (code "112") (name "unconnected-(U$2-UART4_CTSN-Pad35)") (class "Default")
      (node (ref "U$2") (pin "35") (pinfunction "UART4_CTSN_35") (pintype "passive"))
    )
    (net (code "113") (name "unconnected-(U$2-UART4_RTSN-Pad33)") (class "Default")
      (node (ref "U$2") (pin "33") (pinfunction "UART4_RTSN_33") (pintype "passive"))
    )
    (net (code "114") (name "unconnected-(U$2-UART4_RXD-Pad57)") (class "Default")
      (node (ref "U$2") (pin "57") (pinfunction "UART4_RXD_57") (pintype "passive"))
    )
    (net (code "115") (name "unconnected-(U$2-UART4_TXD-Pad59)") (class "Default")
      (node (ref "U$2") (pin "59") (pinfunction "UART4_TXD_59") (pintype "passive"))
    )
    (net (code "116") (name "unconnected-(U$2-UART5_CTSN-Pad31)") (class "Default")
      (node (ref "U$2") (pin "31") (pinfunction "UART5_CTSN_31") (pintype "passive"))
    )
    (net (code "117") (name "unconnected-(U$2-UART5_RTSN-Pad32)") (class "Default")
      (node (ref "U$2") (pin "32") (pinfunction "UART5_RTSN_32") (pintype "passive"))
    )
    (net (code "118") (name "unconnected-(U$2-UART5_TXD-Pad37)") (class "Default")
      (node (ref "U$2") (pin "37") (pinfunction "UART5_TXD_37") (pintype "passive"))
    )
    (net (code "119") (name "unconnected-(U$2-VDD_ADC-Pad78)") (class "Default")
      (node (ref "U$2") (pin "78") (pinfunction "VDD_ADC_78") (pintype "passive"))
    )
    (net (code "120") (name "unconnected-(U1-Pad8)") (class "Default")
      (node (ref "U1") (pin "8") (pinfunction "8_8") (pintype "bidirectional"))
    )
    (net (code "121") (name "unconnected-(U1-Pad10)") (class "Default")
      (node (ref "U1") (pin "10") (pinfunction "10_10") (pintype "bidirectional"))
    )
  )
)
